# MCU.net
KiCad netlist of a schematic drawn in Altium Designer
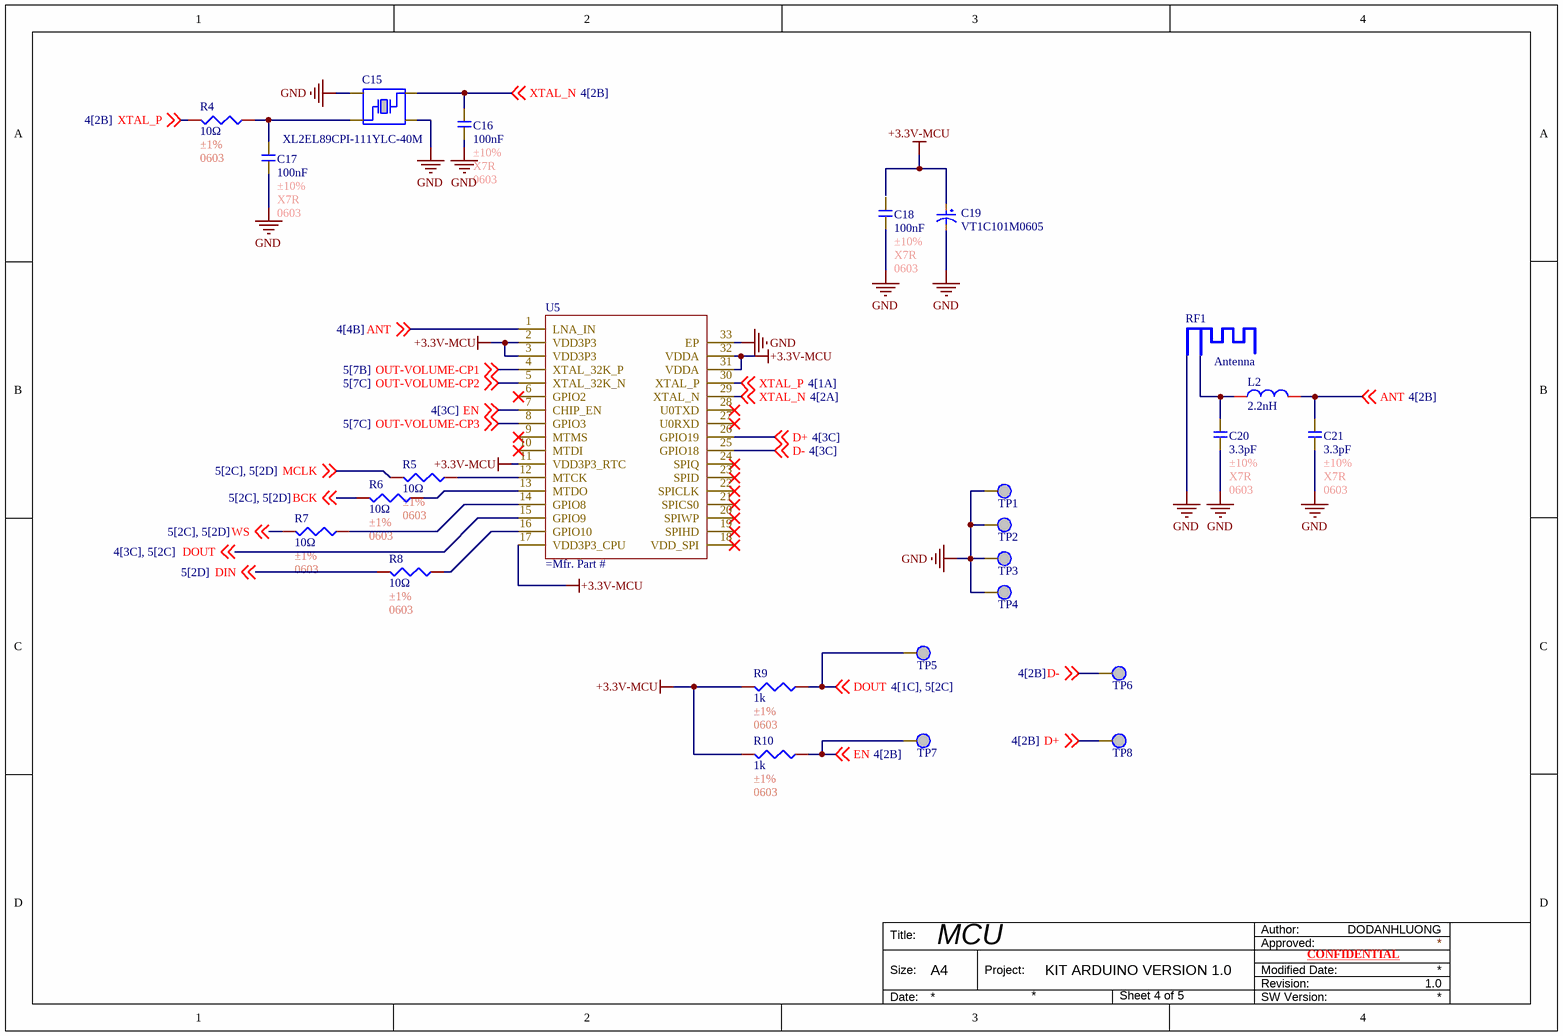
[diagram p0: MCU.SchDoc]

(export (version "E")
  (design (tool "Eeschema 10.0.6"))
  (components
    (comp (ref "C15")
      (value "XL2EL89CPI-111YLC-40M")
      (footprint "XL2EL89CPI-111YLC-40M")
      (description "Crystal Oscillator 15pF SMD3225-4P Crystals RoHS")
      (fields (field (name "MANUFACTURER") "YXC Crystal Oscillators") (field (name "LCSC PART #") "C5444549"))
      (libsource (lib "Oscillator") (part "XL2EL89CPI-111YLC-40M"))
    )
    (comp (ref "C16")
      (value "100nF")
      (footprint "C0603")
      (description "50V 100nF X7R ±10% 0603 Multilayer Ceramic Capacitors MLCC - SMD/SMT ROHS")
      (fields
        (field (name "MANUFACTURER") "YAGEO")
        (field (name "MFR. PART #") "CC0603KRX7R9BB104")
        (field (name "TOLERANCE") "±10%")
        (field (name "TEMPERATURE COEFFICIENT") "X7R")
        (field (name "PACKAGE") "0603")
      )
      (libsource (lib "DSP_VERSION_1.0") (part "C0603_100nF_±10%_X7R"))
    )
    (comp (ref "C17")
      (value "100nF")
      (footprint "C0603")
      (description "50V 100nF X7R ±10% 0603 Multilayer Ceramic Capacitors MLCC - SMD/SMT ROHS")
      (fields
        (field (name "MANUFACTURER") "YAGEO")
        (field (name "MFR. PART #") "CC0603KRX7R9BB104")
        (field (name "TOLERANCE") "±10%")
        (field (name "TEMPERATURE COEFFICIENT") "X7R")
        (field (name "PACKAGE") "0603")
      )
      (libsource (lib "DSP_VERSION_1.0") (part "C0603_100nF_±10%_X7R"))
    )
    (comp (ref "C18")
      (value "100nF")
      (footprint "C0603")
      (description "50V 100nF X7R ±10% 0603 Multilayer Ceramic Capacitors MLCC - SMD/SMT ROHS")
      (fields
        (field (name "MANUFACTURER") "YAGEO")
        (field (name "MFR. PART #") "CC0603KRX7R9BB104")
        (field (name "TOLERANCE") "±10%")
        (field (name "TEMPERATURE COEFFICIENT") "X7R")
        (field (name "PACKAGE") "0603")
      )
      (libsource (lib "DSP_VERSION_1.0") (part "C0603_100nF_±10%_X7R"))
    )
    (comp (ref "C19")
      (value "VT1C101M0605")
      (footprint "C_100uF_16V_Aluminum")
      (description "100uF 16V ±20% 63mA@120Hz SMD,D6.3xL5.4mm Aluminum Electrolytic Capacitors RoHS")
      (fields (field (name "MANUFACTURER") "ROQANG") (field (name "LCSC PART #") "C90273"))
      (libsource (lib "Capital") (part "C_100uF_16V_aluminum"))
    )
    (comp (ref "C20")
      (value "3.3pF")
      (footprint "C0603")
      (description "50V 100nF X7R ±10% 0603 Multilayer Ceramic Capacitors MLCC - SMD/SMT ROHS")
      (fields
        (field (name "MANUFACTURER") "YAGEO")
        (field (name "MFR. PART #") "CC0603KRX7R9BB104")
        (field (name "TOLERANCE") "±10%")
        (field (name "TEMPERATURE COEFFICIENT") "X7R")
        (field (name "PACKAGE") "0603")
      )
      (libsource (lib "DSP_VERSION_1.0") (part "C0603_100nF_±10%_X7R"))
    )
    (comp (ref "C21")
      (value "3.3pF")
      (footprint "C0603")
      (description "50V 100nF X7R ±10% 0603 Multilayer Ceramic Capacitors MLCC - SMD/SMT ROHS")
      (fields
        (field (name "MANUFACTURER") "YAGEO")
        (field (name "MFR. PART #") "CC0603KRX7R9BB104")
        (field (name "TOLERANCE") "±10%")
        (field (name "TEMPERATURE COEFFICIENT") "X7R")
        (field (name "PACKAGE") "0603")
      )
      (libsource (lib "DSP_VERSION_1.0") (part "C0603_100nF_±10%_X7R"))
    )
    (comp (ref "L2")
      (value "2.2nH")
      (footprint "CD43")
      (description "1.15A 10uH Unshielded Inductor ±20% SMD,4x4.5mm Power Inductors ROHS")
      (fields (field (name "MANUFACTURER") "ZE") (field (name "MFR. PART #") "CD43-100M"))
      (libsource (lib "Inductor") (part "CD4-10UH"))
    )
    (comp (ref "R4")
      (value "10Ω")
      (footprint "R0603")
      (description "62.5mW Thick Film Resistor 50V ±1% ±200ppm/℃ 10Ω 0402 Chip Resistor - Surface Mount ROHS")
      (fields
        (field (name "MANUFACTURER") "YAGEO")
        (field (name "MFR. PART #") "RC0402FR-0710RL")
        (field (name "TOLERANCE") "±1%")
        (field (name "PACKAGE") "0603")
      )
      (libsource (lib "Resistor") (part "R0603_10Ω_±1%"))
    )
    (comp (ref "R5")
      (value "10Ω")
      (footprint "R0603")
      (description "62.5mW Thick Film Resistor 50V ±1% ±200ppm/℃ 10Ω 0402 Chip Resistor - Surface Mount ROHS")
      (fields
        (field (name "MANUFACTURER") "YAGEO")
        (field (name "MFR. PART #") "RC0402FR-0710RL")
        (field (name "TOLERANCE") "±1%")
        (field (name "PACKAGE") "0603")
      )
      (libsource (lib "Resistor") (part "R0603_10Ω_±1%"))
    )
    (comp (ref "R6")
      (value "10Ω")
      (footprint "R0603")
      (description "62.5mW Thick Film Resistor 50V ±1% ±200ppm/℃ 10Ω 0402 Chip Resistor - Surface Mount ROHS")
      (fields
        (field (name "MANUFACTURER") "YAGEO")
        (field (name "MFR. PART #") "RC0402FR-0710RL")
        (field (name "TOLERANCE") "±1%")
        (field (name "PACKAGE") "0603")
      )
      (libsource (lib "Resistor") (part "R0603_10Ω_±1%"))
    )
    (comp (ref "R7")
      (value "10Ω")
      (footprint "R0603")
      (description "62.5mW Thick Film Resistor 50V ±1% ±200ppm/℃ 10Ω 0402 Chip Resistor - Surface Mount ROHS")
      (fields
        (field (name "MANUFACTURER") "YAGEO")
        (field (name "MFR. PART #") "RC0402FR-0710RL")
        (field (name "TOLERANCE") "±1%")
        (field (name "PACKAGE") "0603")
      )
      (libsource (lib "Resistor") (part "R0603_10Ω_±1%"))
    )
    (comp (ref "R8")
      (value "10Ω")
      (footprint "R0603")
      (description "62.5mW Thick Film Resistor 50V ±1% ±200ppm/℃ 10Ω 0402 Chip Resistor - Surface Mount ROHS")
      (fields
        (field (name "MANUFACTURER") "YAGEO")
        (field (name "MFR. PART #") "RC0402FR-0710RL")
        (field (name "TOLERANCE") "±1%")
        (field (name "PACKAGE") "0603")
      )
      (libsource (lib "Resistor") (part "R0603_10Ω_±1%"))
    )
    (comp (ref "R9")
      (value "1k")
      (footprint "R0603")
      (description "62.5mW Thick Film Resistor 50V ±1% ±200ppm/℃ 10Ω 0402 Chip Resistor - Surface Mount ROHS")
      (fields
        (field (name "MANUFACTURER") "YAGEO")
        (field (name "MFR. PART #") "RC0402FR-0710RL")
        (field (name "TOLERANCE") "±1%")
        (field (name "PACKAGE") "0603")
      )
      (libsource (lib "Resistor") (part "R0603_10Ω_±1%"))
    )
    (comp (ref "R10")
      (value "1k")
      (footprint "R0603")
      (description "62.5mW Thick Film Resistor 50V ±1% ±200ppm/℃ 10Ω 0402 Chip Resistor - Surface Mount ROHS")
      (fields
        (field (name "MANUFACTURER") "YAGEO")
        (field (name "MFR. PART #") "RC0402FR-0710RL")
        (field (name "TOLERANCE") "±1%")
        (field (name "PACKAGE") "0603")
      )
      (libsource (lib "Resistor") (part "R0603_10Ω_±1%"))
    )
    (comp (ref "RF1")
      (value "Antenna")
      (footprint "2.4GHZ-50OHMS_v1.1")
      (libsource (lib "Antenna") (part "Antenna"))
    )
    (comp (ref "TP1") (value "TP") (footprint "TP") (libsource (lib "Other") (part "TP")))
    (comp (ref "TP2") (value "TP") (footprint "TP") (libsource (lib "Other") (part "TP")))
    (comp (ref "TP3") (value "TP") (footprint "TP") (libsource (lib "Other") (part "TP")))
    (comp (ref "TP4") (value "TP") (footprint "TP") (libsource (lib "Other") (part "TP")))
    (comp (ref "TP5") (value "TP") (footprint "TP") (libsource (lib "Other") (part "TP")))
    (comp (ref "TP6") (value "TP") (footprint "TP") (libsource (lib "Other") (part "TP")))
    (comp (ref "TP7") (value "TP") (footprint "TP") (libsource (lib "Other") (part "TP")))
    (comp (ref "TP8") (value "TP") (footprint "TP") (libsource (lib "Other") (part "TP")))
    (comp (ref "U5")
      (value "~")
      (footprint "ESP32-C3")
      (description "Others 160MHz QFN-32-EP(5x5) RF Transceiver Modules and Modems RoHS")
      (fields (field (name "MANUFACTURER") "ESPRESSIF") (field (name "LCSC PART #") "C2838500"))
      (libsource (lib "MCU") (part "ESP32-C3"))
    )
  )
  (nets
    (net (code "1") (name "+3.3V-MCU") (class "Default")
      (node (ref "C19") (pin "1") (pinfunction "1_1") (pintype "passive"))
      (node (ref "R10") (pin "2") (pinfunction "2_2") (pintype "passive"))
      (node (ref "R9") (pin "2") (pinfunction "2_2") (pintype "passive"))
      (node (ref "U5") (pin "11") (pinfunction "VDD3P3_RTC_11") (pintype "passive"))
      (node (ref "U5") (pin "17") (pinfunction "VDD3P3_CPU_17") (pintype "passive"))
      (node (ref "U5") (pin "2") (pinfunction "VDD3P3_2") (pintype "passive"))
      (node (ref "U5") (pin "3") (pinfunction "VDD3P3_3") (pintype "passive"))
      (node (ref "U5") (pin "31") (pinfunction "VDDA_31") (pintype "passive"))
      (node (ref "U5") (pin "32") (pinfunction "VDDA_32") (pintype "passive"))
    )
    (net (code "2") (name "ANT") (class "Default")
      (node (ref "C21") (pin "2") (pinfunction "2_2") (pintype "passive"))
      (node (ref "L2") (pin "2") (pinfunction "2_2") (pintype "passive"))
      (node (ref "U5") (pin "1") (pinfunction "LNA_IN_1") (pintype "passive"))
    )
    (net (code "3") (name "BCK") (class "Default")
      (node (ref "R6") (pin "2") (pinfunction "2_2") (pintype "passive"))
    )
    (net (code "4") (name "D+") (class "Default")
      (node (ref "TP8") (pin "1") (pinfunction "1_1") (pintype "passive"))
      (node (ref "U5") (pin "26") (pinfunction "GPIO19_26") (pintype "passive"))
    )
    (net (code "5") (name "D-") (class "Default")
      (node (ref "TP6") (pin "1") (pinfunction "1_1") (pintype "passive"))
      (node (ref "U5") (pin "25") (pinfunction "GPIO18_25") (pintype "passive"))
    )
    (net (code "6") (name "DIN") (class "Default")
      (node (ref "R8") (pin "2") (pinfunction "2_2") (pintype "passive"))
    )
    (net (code "7") (name "DOUT") (class "Default")
      (node (ref "R9") (pin "1") (pinfunction "1_1") (pintype "passive"))
      (node (ref "TP5") (pin "1") (pinfunction "1_1") (pintype "passive"))
      (node (ref "U5") (pin "15") (pinfunction "GPIO9_15") (pintype "passive"))
    )
    (net (code "8") (name "EN") (class "Default")
      (node (ref "R10") (pin "1") (pinfunction "1_1") (pintype "passive"))
      (node (ref "TP7") (pin "1") (pinfunction "1_1") (pintype "passive"))
      (node (ref "U5") (pin "7") (pinfunction "CHIP_EN_7") (pintype "passive"))
    )
    (net (code "9") (name "GND") (class "Default")
      (node (ref "C15") (pin "2") (pinfunction "2_2") (pintype "passive"))
      (node (ref "C15") (pin "4") (pinfunction "4_4") (pintype "passive"))
      (node (ref "C16") (pin "1") (pinfunction "1_1") (pintype "passive"))
      (node (ref "C17") (pin "1") (pinfunction "1_1") (pintype "passive"))
      (node (ref "C18") (pin "1") (pinfunction "1_1") (pintype "passive"))
      (node (ref "C19") (pin "2") (pinfunction "2_2") (pintype "passive"))
      (node (ref "C20") (pin "1") (pinfunction "1_1") (pintype "passive"))
      (node (ref "C21") (pin "1") (pinfunction "1_1") (pintype "passive"))
      (node (ref "RF1") (pin "2") (pinfunction "2_2") (pintype "passive"))
      (node (ref "TP1") (pin "1") (pinfunction "1_1") (pintype "passive"))
      (node (ref "TP2") (pin "1") (pinfunction "1_1") (pintype "passive"))
      (node (ref "TP3") (pin "1") (pinfunction "1_1") (pintype "passive"))
      (node (ref "TP4") (pin "1") (pinfunction "1_1") (pintype "passive"))
      (node (ref "U5") (pin "33") (pinfunction "EP_33") (pintype "passive"))
    )
    (net (code "10") (name "MCLK") (class "Default")
      (node (ref "R5") (pin "2") (pinfunction "2_2") (pintype "passive"))
    )
    (net (code "11") (name "Net-(C15-Pad1)") (class "Default")
      (node (ref "C15") (pin "1") (pinfunction "1_1") (pintype "passive"))
      (node (ref "C17") (pin "2") (pinfunction "2_2") (pintype "passive"))
      (node (ref "R4") (pin "1") (pinfunction "1_1") (pintype "passive"))
    )
    (net (code "12") (name "Net-(C20-Pad2)") (class "Default")
      (node (ref "C20") (pin "2") (pinfunction "2_2") (pintype "passive"))
      (node (ref "L2") (pin "1") (pinfunction "1_1") (pintype "passive"))
      (node (ref "RF1") (pin "1") (pinfunction "1_1") (pintype "passive"))
    )
    (net (code "13") (name "Net-(U5-GPIO8)") (class "Default")
      (node (ref "R7") (pin "1") (pinfunction "1_1") (pintype "passive"))
      (node (ref "U5") (pin "14") (pinfunction "GPIO8_14") (pintype "passive"))
    )
    (net (code "14") (name "Net-(U5-GPIO10)") (class "Default")
      (node (ref "R8") (pin "1") (pinfunction "1_1") (pintype "passive"))
      (node (ref "U5") (pin "16") (pinfunction "GPIO10_16") (pintype "passive"))
    )
    (net (code "15") (name "Net-(U5-MTCK)") (class "Default")
      (node (ref "R5") (pin "1") (pinfunction "1_1") (pintype "passive"))
      (node (ref "U5") (pin "12") (pinfunction "MTCK_12") (pintype "passive"))
    )
    (net (code "16") (name "Net-(U5-MTDO)") (class "Default")
      (node (ref "R6") (pin "1") (pinfunction "1_1") (pintype "passive"))
      (node (ref "U5") (pin "13") (pinfunction "MTDO_13") (pintype "passive"))
    )
    (net (code "17") (name "OUT-VOLUME-CP1") (class "Default")
      (node (ref "U5") (pin "4") (pinfunction "XTAL_32K_P_4") (pintype "passive"))
    )
    (net (code "18") (name "OUT-VOLUME-CP2") (class "Default")
      (node (ref "U5") (pin "5") (pinfunction "XTAL_32K_N_5") (pintype "passive"))
    )
    (net (code "19") (name "OUT-VOLUME-CP3") (class "Default")
      (node (ref "U5") (pin "8") (pinfunction "GPIO3_8") (pintype "passive"))
    )
    (net (code "20") (name "WS") (class "Default")
      (node (ref "R7") (pin "2") (pinfunction "2_2") (pintype "passive"))
    )
    (net (code "21") (name "XTAL_N") (class "Default")
      (node (ref "C15") (pin "3") (pinfunction "3_3") (pintype "passive"))
      (node (ref "C16") (pin "2") (pinfunction "2_2") (pintype "passive"))
      (node (ref "U5") (pin "29") (pinfunction "XTAL_N_29") (pintype "passive"))
    )
    (net (code "22") (name "XTAL_P") (class "Default")
      (node (ref "R4") (pin "2") (pinfunction "2_2") (pintype "passive"))
      (node (ref "U5") (pin "30") (pinfunction "XTAL_P_30") (pintype "passive"))
    )
    (net (code "23") (name "unconnected-(C18-Pad2)") (class "Default")
      (node (ref "C18") (pin "2") (pinfunction "2_2") (pintype "passive"))
    )
    (net (code "24") (name "unconnected-(U5-GPIO2-Pad6)") (class "Default")
      (node (ref "U5") (pin "6") (pinfunction "GPIO2_6") (pintype "passive+no_connect"))
    )
    (net (code "25") (name "unconnected-(U5-MTDI-Pad10)") (class "Default")
      (node (ref "U5") (pin "10") (pinfunction "MTDI_10") (pintype "passive+no_connect"))
    )
    (net (code "26") (name "unconnected-(U5-MTMS-Pad9)") (class "Default")
      (node (ref "U5") (pin "9") (pinfunction "MTMS_9") (pintype "passive+no_connect"))
    )
    (net (code "27") (name "unconnected-(U5-SPICLK-Pad22)") (class "Default")
      (node (ref "U5") (pin "22") (pinfunction "SPICLK_22") (pintype "passive+no_connect"))
    )
    (net (code "28") (name "unconnected-(U5-SPICS0-Pad21)") (class "Default")
      (node (ref "U5") (pin "21") (pinfunction "SPICS0_21") (pintype "passive+no_connect"))
    )
    (net (code "29") (name "unconnected-(U5-SPID-Pad23)") (class "Default")
      (node (ref "U5") (pin "23") (pinfunction "SPID_23") (pintype "passive+no_connect"))
    )
    (net (code "30") (name "unconnected-(U5-SPIHD-Pad19)") (class "Default")
      (node (ref "U5") (pin "19") (pinfunction "SPIHD_19") (pintype "passive+no_connect"))
    )
    (net (code "31") (name "unconnected-(U5-SPIQ-Pad24)") (class "Default")
      (node (ref "U5") (pin "24") (pinfunction "SPIQ_24") (pintype "passive+no_connect"))
    )
    (net (code "32") (name "unconnected-(U5-SPIWP-Pad20)") (class "Default")
      (node (ref "U5") (pin "20") (pinfunction "SPIWP_20") (pintype "passive+no_connect"))
    )
    (net (code "33") (name "unconnected-(U5-U0RXD-Pad27)") (class "Default")
      (node (ref "U5") (pin "27") (pinfunction "U0RXD_27") (pintype "passive+no_connect"))
    )
    (net (code "34") (name "unconnected-(U5-U0TXD-Pad28)") (class "Default")
      (node (ref "U5") (pin "28") (pinfunction "U0TXD_28") (pintype "passive+no_connect"))
    )
    (net (code "35") (name "unconnected-(U5-VDD_SPI-Pad18)") (class "Default")
      (node (ref "U5") (pin "18") (pinfunction "VDD_SPI_18") (pintype "passive+no_connect"))
    )
  )
)
